# ATMEGA.net
KiCad netlist of a schematic drawn in Altium Designer
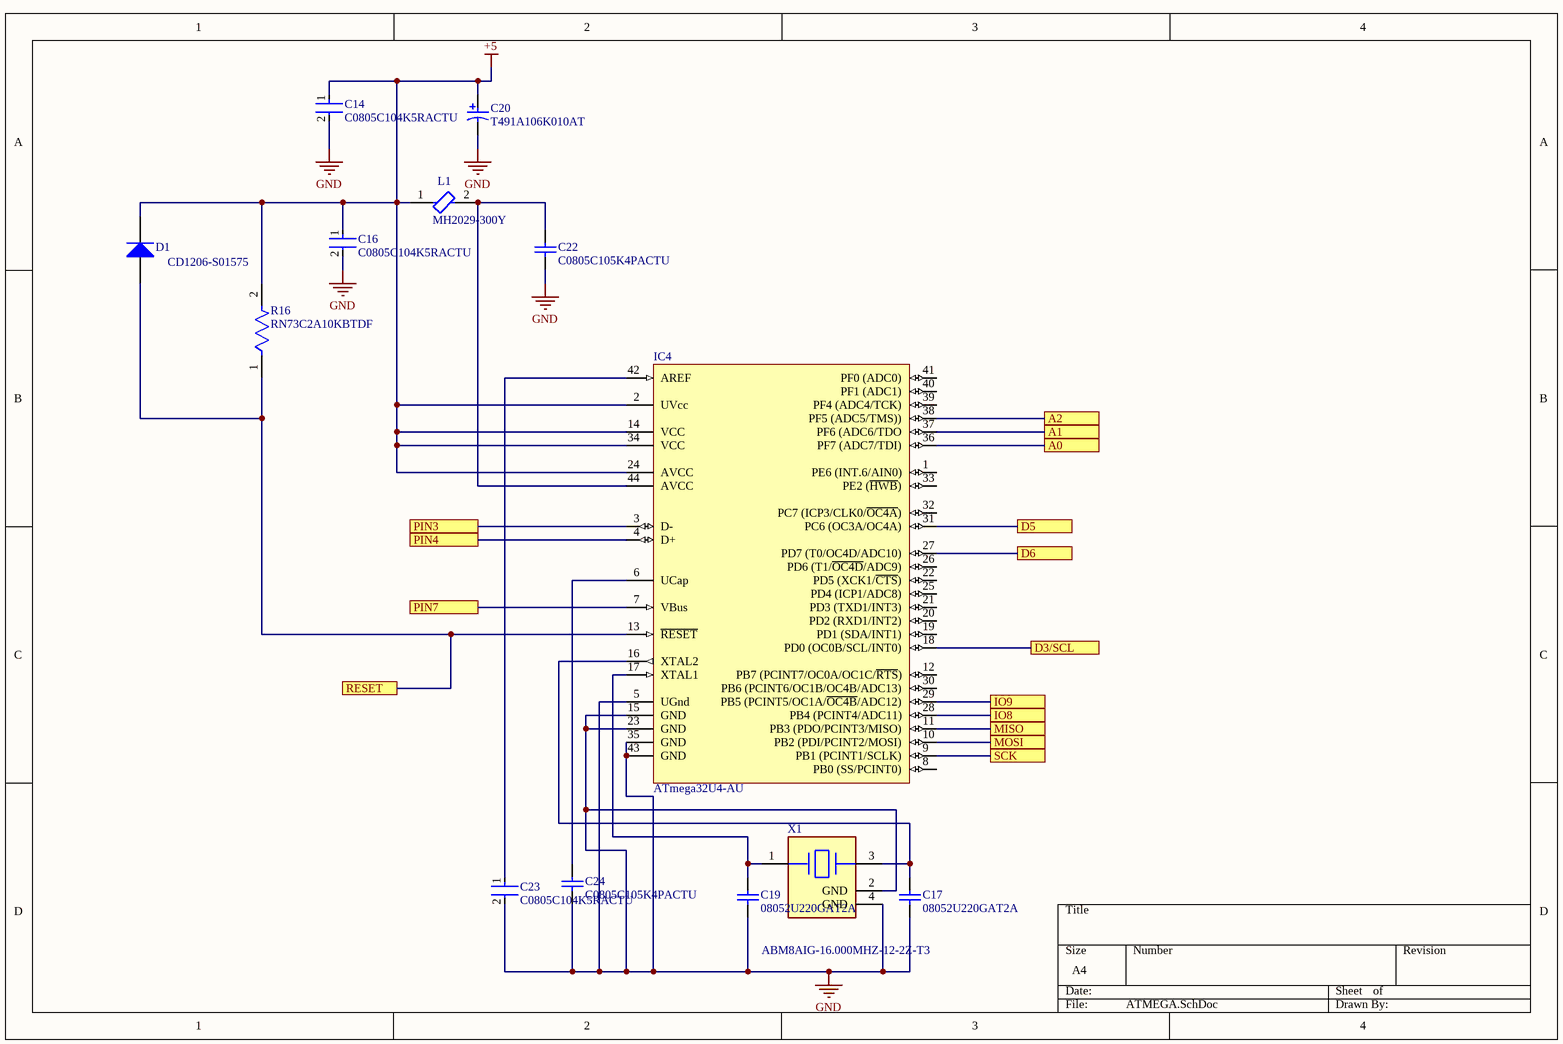
[diagram p0: ATMEGA.SchDoc]

(export (version "E")
  (design (tool "Eeschema 10.0.6"))
  (components
    (comp (ref "C14")
      (value "C0805C104K5RACTU")
      (footprint "FP-C0805C-DN-MFG")
      (description "CAP CER 0.1UF 50V X7R 0805")
      (fields
        (field (name "MANUFACTURER") "KEMET")
        (field (name "OCTOPART") "https://octopart.com/c0805c104k5ractu-kemet-143926")
      )
      (libsource (lib "Altium Content Vault") (part "b4654b650e69147ec39a6b967a45e02"))
    )
    (comp (ref "C16")
      (value "C0805C104K5RACTU")
      (footprint "FP-C0805C-DN-MFG")
      (description "CAP CER 0.1UF 50V X7R 0805")
      (fields
        (field (name "MANUFACTURER") "KEMET")
        (field (name "OCTOPART") "https://octopart.com/c0805c104k5ractu-kemet-143926")
      )
      (libsource (lib "Altium Content Vault") (part "b4654b650e69147ec39a6b967a45e02"))
    )
    (comp (ref "C17")
      (value "08052U220GAT2A")
      (footprint "CAPC2013X115X51NL20T26")
      (fields (field (name "MANUFACTURER") "AVX Interconnect / Elco"))
      (libsource (lib "Altium Content Vault") (part "CAP"))
    )
    (comp (ref "C19")
      (value "08052U220GAT2A")
      (footprint "CAPC2013X115X51NL20T26")
      (fields (field (name "MANUFACTURER") "AVX Interconnect / Elco"))
      (libsource (lib "Altium Content Vault") (part "CAP"))
    )
    (comp (ref "C20")
      (value "T491A106K010AT")
      (footprint "KEMT-A-3216-18-2_M")
      (description "Capacitor, Tantalum, 10 uF, +/- 10%, 10 V, -55 to 125 degC, 2-Pin SMD (1206), RoHS, Tape and Reel")
      (fields (field (name "TOLERANCE") "±10%") (field (name "MANUFACTURER") "Kemet"))
      (libsource (lib "Altium Content Vault") (part "CAP-P-2"))
    )
    (comp (ref "C22")
      (value "C0805C105K4PACTU")
      (footprint "CAPC2013X145X50LL20T25")
      (fields (field (name "MANUFACTURER") "Kemet"))
      (libsource (lib "Altium Content Vault") (part "CAP"))
    )
    (comp (ref "C23")
      (value "C0805C104K5RACTU")
      (footprint "FP-C0805C-DN-MFG")
      (description "CAP CER 0.1UF 50V X7R 0805")
      (fields
        (field (name "MANUFACTURER") "KEMET")
        (field (name "OCTOPART") "https://octopart.com/c0805c104k5ractu-kemet-143926")
      )
      (libsource (lib "Altium Content Vault") (part "b4654b650e69147ec39a6b967a45e02"))
    )
    (comp (ref "C24")
      (value "C0805C105K4PACTU")
      (footprint "CAPC2013X145X50LL20T25")
      (fields (field (name "MANUFACTURER") "Kemet"))
      (libsource (lib "Altium Content Vault") (part "CAP"))
    )
    (comp (ref "D1")
      (value "CD1206-S01575")
      (footprint "BOUR-CD1206-S01575-2_L")
      (description "75 V Small Signal Switching Diode, 150 mA, 2.5 uA, 1026 Molded Package, RoHS, Tape and Reel")
      (fields (field (name "MANUFACTURER") "Bourns"))
      (libsource (lib "Altium Content Vault") (part "BOUR-A1K2-2"))
    )
    (comp (ref "IC4")
      (value "ATmega32U4-AU")
      (footprint "44ML_M")
      (libsource (lib "Altium Content Vault") (part "MC-8B-ATM16U4-SQ44"))
    )
    (comp (ref "L1")
      (value "MH2029-300Y")
      (footprint "FP-MH2029-MFG")
      (description "FERRITE BEAD 30 OHM 0805 1LN")
      (fields
        (field (name "OCTOPART") "https://octopart.com/mh2029-300y-bourns-756929")
        (field (name "MANUFACTURER") "Bourns")
      )
      (libsource (lib "Altium Content Vault") (part "5f30dd21d616792df468990f7003faa"))
    )
    (comp (ref "R16")
      (value "RN73C2A10KBTDF")
      (footprint "FP-RN732A-MFG")
      (description "SMD Chip Resistor, Thin Film, 10KΩ, 100 V, 0805 [2012 Metric], 100 mW, 0.1%, RN73 Series")
      (fields
        (field (name "OCTOPART") "https://octopart.com/rn73c2a10kbtdf-te+connectivity-21400356")
        (field (name "MANUFACTURER") "TE Connectivity")
      )
      (libsource (lib "Altium Content Vault") (part "1029c3af85768c4190bb7ad29bc67b5"))
    )
    (comp (ref "X1")
      (value "ABM8AIG-16.000MHZ-12-2Z-T3")
      (footprint "FP-ABM8AIG-MFG")
      (description "CRYSTAL 16MHZ 12PF SMD")
      (fields
        (field (name "TOLERANCE") "20ppm")
        (field (name "OCTOPART") "https://octopart.com/abm8aig-16.000mhz-12-2z-t3-abracon-70466545")
      )
      (libsource (lib "Altium Content Vault") (part "8c15b40021980ccd80b46c33e9e0ba6"))
    )
  )
  (nets
    (net (code "1") (name "+5") (class "Default")
      (node (ref "C14") (pin "1") (pinfunction "1_1") (pintype "passive"))
      (node (ref "C16") (pin "1") (pinfunction "1_1") (pintype "passive"))
      (node (ref "C20") (pin "1") (pinfunction "1_1") (pintype "passive"))
      (node (ref "D1") (pin "2") (pinfunction "K_2") (pintype "passive"))
      (node (ref "IC4") (pin "14") (pinfunction "VCC_14") (pintype "power_in"))
      (node (ref "IC4") (pin "2") (pinfunction "UVcc_2") (pintype "power_in"))
      (node (ref "IC4") (pin "24") (pinfunction "AVCC_24") (pintype "power_in"))
      (node (ref "IC4") (pin "34") (pinfunction "VCC_34") (pintype "power_in"))
      (node (ref "L1") (pin "1") (pinfunction "1_1") (pintype "passive"))
      (node (ref "R16") (pin "2") (pinfunction "2_2") (pintype "passive"))
    )
    (net (code "2") (name "/A0") (class "Default")
      (node (ref "IC4") (pin "36") (pinfunction "PF7_(ADC7/TDI)_36") (pintype "bidirectional"))
    )
    (net (code "3") (name "/A1") (class "Default")
      (node (ref "IC4") (pin "37") (pinfunction "PF6_(ADC6/TDO_37") (pintype "bidirectional"))
    )
    (net (code "4") (name "/A2") (class "Default")
      (node (ref "IC4") (pin "38") (pinfunction "PF5_(ADC5/TMS))_38") (pintype "bidirectional"))
    )
    (net (code "5") (name "/D3{slash}SCL") (class "Default")
      (node (ref "IC4") (pin "18") (pinfunction "PD0_(OC0B/SCL/INT0)_18") (pintype "bidirectional"))
    )
    (net (code "6") (name "/D5") (class "Default")
      (node (ref "IC4") (pin "31") (pinfunction "PC6_(OC3A/OC4A)_31") (pintype "bidirectional"))
    )
    (net (code "7") (name "/D6") (class "Default")
      (node (ref "IC4") (pin "27") (pinfunction "PD7_(T0/OC4D/ADC10)_27") (pintype "bidirectional"))
    )
    (net (code "8") (name "/IO8") (class "Default")
      (node (ref "IC4") (pin "28") (pinfunction "PB4_(PCINT4/ADC11)_28") (pintype "bidirectional"))
    )
    (net (code "9") (name "/IO9") (class "Default")
      (node (ref "IC4") (pin "29") (pinfunction "PB5_(PCINT5/OC1A/~{OC4B}/ADC12)_29") (pintype "bidirectional"))
    )
    (net (code "10") (name "/MISO") (class "Default")
      (node (ref "IC4") (pin "11") (pinfunction "PB3_(PDO/PCINT3/MISO)_11") (pintype "bidirectional"))
    )
    (net (code "11") (name "/MOSI") (class "Default")
      (node (ref "IC4") (pin "10") (pinfunction "PB2_(PDI/PCINT2/MOSI)_10") (pintype "bidirectional"))
    )
    (net (code "12") (name "/PIN3") (class "Default")
      (node (ref "IC4") (pin "3") (pinfunction "D-_3") (pintype "bidirectional"))
    )
    (net (code "13") (name "/PIN4") (class "Default")
      (node (ref "IC4") (pin "4") (pinfunction "D+_4") (pintype "bidirectional"))
    )
    (net (code "14") (name "/PIN7") (class "Default")
      (node (ref "IC4") (pin "7") (pinfunction "VBus_7") (pintype "input"))
    )
    (net (code "15") (name "/RESET") (class "Default")
      (node (ref "D1") (pin "1") (pinfunction "A_1") (pintype "passive"))
      (node (ref "IC4") (pin "13") (pinfunction "~{RESET}_13") (pintype "input"))
      (node (ref "R16") (pin "1") (pinfunction "1_1") (pintype "passive"))
    )
    (net (code "16") (name "/SCK") (class "Default")
      (node (ref "IC4") (pin "9") (pinfunction "PB1_(PCINT1/SCLK)_9") (pintype "bidirectional"))
    )
    (net (code "17") (name "GND") (class "Default")
      (node (ref "C14") (pin "2") (pinfunction "2_2") (pintype "passive"))
      (node (ref "C16") (pin "2") (pinfunction "2_2") (pintype "passive"))
      (node (ref "C17") (pin "1") (pinfunction "1_1") (pintype "passive"))
      (node (ref "C19") (pin "1") (pinfunction "1_1") (pintype "passive"))
      (node (ref "C20") (pin "2") (pinfunction "2_2") (pintype "passive"))
      (node (ref "C22") (pin "1") (pinfunction "1_1") (pintype "passive"))
      (node (ref "C23") (pin "2") (pinfunction "2_2") (pintype "passive"))
      (node (ref "C24") (pin "1") (pinfunction "1_1") (pintype "passive"))
      (node (ref "IC4") (pin "15") (pinfunction "GND_15") (pintype "power_in"))
      (node (ref "IC4") (pin "23") (pinfunction "GND_23") (pintype "power_in"))
      (node (ref "IC4") (pin "35") (pinfunction "GND_35") (pintype "power_in"))
      (node (ref "IC4") (pin "43") (pinfunction "GND_43") (pintype "power_in"))
      (node (ref "IC4") (pin "5") (pinfunction "UGnd_5") (pintype "power_in"))
      (node (ref "X1") (pin "2") (pinfunction "GND_2") (pintype "power_in"))
      (node (ref "X1") (pin "4") (pinfunction "GND_4") (pintype "power_in"))
    )
    (net (code "18") (name "Net-(C22-Pad2)") (class "Default")
      (node (ref "C22") (pin "2") (pinfunction "2_2") (pintype "passive"))
      (node (ref "IC4") (pin "44") (pinfunction "AVCC_44") (pintype "power_in"))
      (node (ref "L1") (pin "2") (pinfunction "2_2") (pintype "passive"))
    )
    (net (code "19") (name "Net-(IC4-AREF)") (class "Default")
      (node (ref "C23") (pin "1") (pinfunction "1_1") (pintype "passive"))
      (node (ref "IC4") (pin "42") (pinfunction "AREF_42") (pintype "input"))
    )
    (net (code "20") (name "Net-(IC4-UCap)") (class "Default")
      (node (ref "C24") (pin "2") (pinfunction "2_2") (pintype "passive"))
      (node (ref "IC4") (pin "6") (pinfunction "UCap_6") (pintype "passive"))
    )
    (net (code "21") (name "Net-(IC4-XTAL1)") (class "Default")
      (node (ref "C19") (pin "2") (pinfunction "2_2") (pintype "passive"))
      (node (ref "IC4") (pin "17") (pinfunction "XTAL1_17") (pintype "input"))
      (node (ref "X1") (pin "1") (pinfunction "1_Crystal_1") (pintype "passive"))
    )
    (net (code "22") (name "Net-(IC4-XTAL2)") (class "Default")
      (node (ref "C17") (pin "2") (pinfunction "2_2") (pintype "passive"))
      (node (ref "IC4") (pin "16") (pinfunction "XTAL2_16") (pintype "output"))
      (node (ref "X1") (pin "3") (pinfunction "2_Crystal_3") (pintype "passive"))
    )
    (net (code "23") (name "unconnected-(IC4-PB0_(SS{slash}PCINT0)-Pad8)") (class "Default")
      (node (ref "IC4") (pin "8") (pinfunction "PB0_(SS/PCINT0)_8") (pintype "bidirectional"))
    )
    (net (code "24") (name "unconnected-(IC4-PB6_(PCINT6{slash}OC1B{slash}OC4B{slash}ADC13)-Pad30)") (class "Default")
      (node (ref "IC4") (pin "30") (pinfunction "PB6_(PCINT6/OC1B/OC4B/ADC13)_30") (pintype "bidirectional"))
    )
    (net (code "25") (name "unconnected-(IC4-PB7_(PCINT7{slash}OC0A{slash}OC1C{slash}~{RTS})-Pad12)") (class "Default")
      (node (ref "IC4") (pin "12") (pinfunction "PB7_(PCINT7/OC0A/OC1C/~{RTS})_12") (pintype "bidirectional"))
    )
    (net (code "26") (name "unconnected-(IC4-PC7_(ICP3{slash}CLK0{slash}~{OC4A})-Pad32)") (class "Default")
      (node (ref "IC4") (pin "32") (pinfunction "PC7_(ICP3/CLK0/~{OC4A})_32") (pintype "bidirectional"))
    )
    (net (code "27") (name "unconnected-(IC4-PD1_(SDA{slash}INT1)-Pad19)") (class "Default")
      (node (ref "IC4") (pin "19") (pinfunction "PD1_(SDA/INT1)_19") (pintype "bidirectional"))
    )
    (net (code "28") (name "unconnected-(IC4-PD2_(RXD1{slash}INT2)-Pad20)") (class "Default")
      (node (ref "IC4") (pin "20") (pinfunction "PD2_(RXD1/INT2)_20") (pintype "bidirectional"))
    )
    (net (code "29") (name "unconnected-(IC4-PD3_(TXD1{slash}INT3)-Pad21)") (class "Default")
      (node (ref "IC4") (pin "21") (pinfunction "PD3_(TXD1/INT3)_21") (pintype "bidirectional"))
    )
    (net (code "30") (name "unconnected-(IC4-PD4_(ICP1{slash}ADC8)-Pad25)") (class "Default")
      (node (ref "IC4") (pin "25") (pinfunction "PD4_(ICP1/ADC8)_25") (pintype "bidirectional"))
    )
    (net (code "31") (name "unconnected-(IC4-PD5_(XCK1{slash}~{CTS})-Pad22)") (class "Default")
      (node (ref "IC4") (pin "22") (pinfunction "PD5_(XCK1/~{CTS})_22") (pintype "bidirectional"))
    )
    (net (code "32") (name "unconnected-(IC4-PD6_(T1{slash}~{OC4D}{slash}ADC9)-Pad26)") (class "Default")
      (node (ref "IC4") (pin "26") (pinfunction "PD6_(T1/~{OC4D}/ADC9)_26") (pintype "bidirectional"))
    )
    (net (code "33") (name "unconnected-(IC4-PE2_(~{HWB})-Pad33)") (class "Default")
      (node (ref "IC4") (pin "33") (pinfunction "PE2_(~{HWB})_33") (pintype "bidirectional"))
    )
    (net (code "34") (name "unconnected-(IC4-PE6_(INT.6{slash}AIN0)-Pad1)") (class "Default")
      (node (ref "IC4") (pin "1") (pinfunction "PE6_(INT.6/AIN0)_1") (pintype "bidirectional"))
    )
    (net (code "35") (name "unconnected-(IC4-PF0_(ADC0)-Pad41)") (class "Default")
      (node (ref "IC4") (pin "41") (pinfunction "PF0_(ADC0)_41") (pintype "bidirectional"))
    )
    (net (code "36") (name "unconnected-(IC4-PF1_(ADC1)-Pad40)") (class "Default")
      (node (ref "IC4") (pin "40") (pinfunction "PF1_(ADC1)_40") (pintype "bidirectional"))
    )
    (net (code "37") (name "unconnected-(IC4-PF4_(ADC4{slash}TCK)-Pad39)") (class "Default")
      (node (ref "IC4") (pin "39") (pinfunction "PF4_(ADC4/TCK)_39") (pintype "bidirectional"))
    )
  )
)
